# Sheet1.net
KiCad netlist of a schematic drawn in Altium Designer
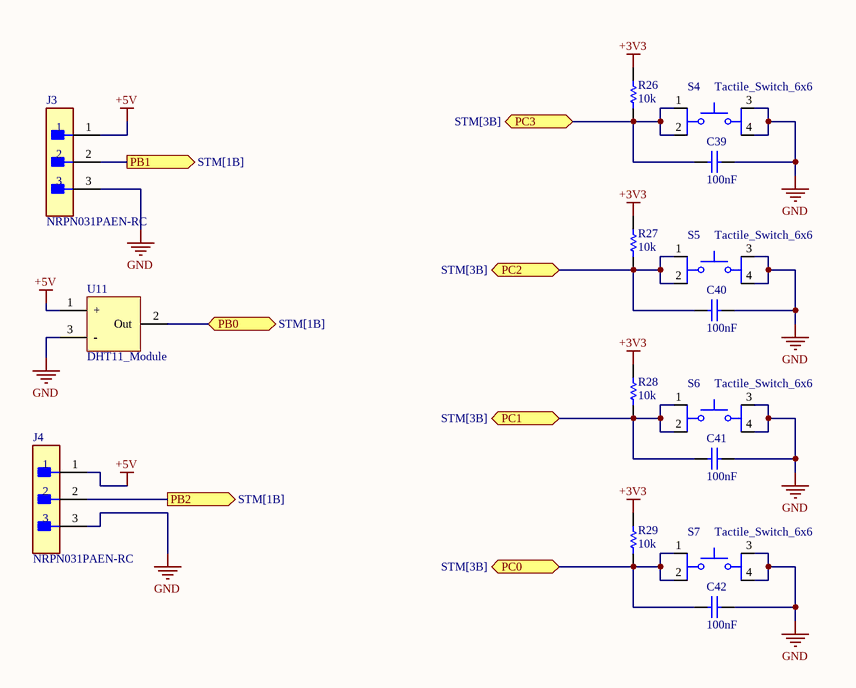
[diagram p0: Sheet1.SchDoc]

(export (version "E")
  (design (tool "Eeschema 10.0.6"))
  (components
    (comp (ref "C39")
      (value "100nF")
      (footprint "CAP_0603")
      (description "CAP, size 0603, 100nF")
      (libsource (lib "SMIOT_Lib_Schematic") (part "01060310410"))
    )
    (comp (ref "C40")
      (value "100nF")
      (footprint "CAP_0603")
      (description "CAP, size 0603, 100nF")
      (libsource (lib "SMIOT_Lib_Schematic") (part "01060310410"))
    )
    (comp (ref "C41")
      (value "100nF")
      (footprint "CAP_0603")
      (description "CAP, size 0603, 100nF")
      (libsource (lib "SMIOT_Lib_Schematic") (part "01060310410"))
    )
    (comp (ref "C42")
      (value "100nF")
      (footprint "CAP_0603")
      (description "CAP, size 0603, 100nF")
      (libsource (lib "SMIOT_Lib_Schematic") (part "01060310410"))
    )
    (comp (ref "J3")
      (value "NRPN031PAEN-RC")
      (footprint "FP-NRPN031PAEN-RC-MFG")
      (description "CONN HEADER VERT 3POS 2MM")
      (fields
        (field (name "OCTOPART") "https://octopart.com/nrpn031paen-rc-sullins-12817732")
        (field (name "MANUFACTURER") "Sullins")
      )
      (libsource (lib "Components - 31.10.24 - 03.11") (part "CMP-25680-000021-1"))
    )
    (comp (ref "J4")
      (value "NRPN031PAEN-RC")
      (footprint "FP-NRPN031PAEN-RC-MFG")
      (description "CONN HEADER VERT 3POS 2MM")
      (fields
        (field (name "OCTOPART") "https://octopart.com/nrpn031paen-rc-sullins-12817732")
        (field (name "MANUFACTURER") "Sullins")
      )
      (libsource (lib "Components - 31.10.24 - 03.11") (part "CMP-25680-000021-1"))
    )
    (comp (ref "R26")
      (value "10k")
      (footprint "resistor_0603")
      (description "RES, 10k Ohm, size 0603, 1%")
      (libsource (lib "SMIOT_Lib_Schematic") (part "0006031031"))
    )
    (comp (ref "R27")
      (value "10k")
      (footprint "resistor_0603")
      (description "RES, 10k Ohm, size 0603, 1%")
      (libsource (lib "SMIOT_Lib_Schematic") (part "0006031031"))
    )
    (comp (ref "R28")
      (value "10k")
      (footprint "resistor_0603")
      (description "RES, 10k Ohm, size 0603, 1%")
      (libsource (lib "SMIOT_Lib_Schematic") (part "0006031031"))
    )
    (comp (ref "R29")
      (value "10k")
      (footprint "resistor_0603")
      (description "RES, 10k Ohm, size 0603, 1%")
      (libsource (lib "SMIOT_Lib_Schematic") (part "0006031031"))
    )
    (comp (ref "S4")
      (value "Tactile_Switch_6x6")
      (footprint "Tactile_Switch_6x6")
      (description "Tactile Switch, 6x6mm")
      (libsource (lib "SMIOT_Lib_Schematic") (part "Tactile_Switch_6x6"))
    )
    (comp (ref "S5")
      (value "Tactile_Switch_6x6")
      (footprint "Tactile_Switch_6x6")
      (description "Tactile Switch, 6x6mm")
      (libsource (lib "SMIOT_Lib_Schematic") (part "Tactile_Switch_6x6"))
    )
    (comp (ref "S6")
      (value "Tactile_Switch_6x6")
      (footprint "Tactile_Switch_6x6")
      (description "Tactile Switch, 6x6mm")
      (libsource (lib "SMIOT_Lib_Schematic") (part "Tactile_Switch_6x6"))
    )
    (comp (ref "S7")
      (value "Tactile_Switch_6x6")
      (footprint "Tactile_Switch_6x6")
      (description "Tactile Switch, 6x6mm")
      (libsource (lib "SMIOT_Lib_Schematic") (part "Tactile_Switch_6x6"))
    )
    (comp (ref "U11")
      (value "DHT11_Module")
      (footprint "DHT11_Module")
      (description "Temperature & Humidity Sensor, 3.3V-5V, 5mA")
      (libsource (lib "SMIOT_Lib_Schematic") (part "DHT11_Module"))
    )
  )
  (nets
    (net (code "1") (name "+3V3") (class "Default")
      (node (ref "R26") (pin "1") (pinfunction "1_1") (pintype "passive"))
      (node (ref "R27") (pin "1") (pinfunction "1_1") (pintype "passive"))
      (node (ref "R28") (pin "1") (pinfunction "1_1") (pintype "passive"))
      (node (ref "R29") (pin "1") (pinfunction "1_1") (pintype "passive"))
    )
    (net (code "2") (name "+5V") (class "Default")
      (node (ref "J3") (pin "1") (pinfunction "1_1") (pintype "passive"))
      (node (ref "J4") (pin "1") (pinfunction "1_1") (pintype "passive"))
      (node (ref "U11") (pin "1") (pinfunction "+_1") (pintype "passive"))
    )
    (net (code "3") (name "/PB0") (class "Default")
      (node (ref "U11") (pin "2") (pinfunction "Out_2") (pintype "passive"))
    )
    (net (code "4") (name "/PB1") (class "Default")
      (node (ref "J3") (pin "2") (pinfunction "2_2") (pintype "passive"))
    )
    (net (code "5") (name "/PB2") (class "Default")
      (node (ref "J4") (pin "2") (pinfunction "2_2") (pintype "passive"))
    )
    (net (code "6") (name "/PC0") (class "Default")
      (node (ref "C42") (pin "1") (pinfunction "1_1") (pintype "passive"))
      (node (ref "R29") (pin "2") (pinfunction "2_2") (pintype "passive"))
      (node (ref "S7") (pin "1") (pinfunction "1_1") (pintype "passive"))
      (node (ref "S7") (pin "2") (pinfunction "2_2") (pintype "passive"))
    )
    (net (code "7") (name "/PC1") (class "Default")
      (node (ref "C41") (pin "1") (pinfunction "1_1") (pintype "passive"))
      (node (ref "R28") (pin "2") (pinfunction "2_2") (pintype "passive"))
      (node (ref "S6") (pin "1") (pinfunction "1_1") (pintype "passive"))
      (node (ref "S6") (pin "2") (pinfunction "2_2") (pintype "passive"))
    )
    (net (code "8") (name "/PC2") (class "Default")
      (node (ref "C40") (pin "1") (pinfunction "1_1") (pintype "passive"))
      (node (ref "R27") (pin "2") (pinfunction "2_2") (pintype "passive"))
      (node (ref "S5") (pin "1") (pinfunction "1_1") (pintype "passive"))
      (node (ref "S5") (pin "2") (pinfunction "2_2") (pintype "passive"))
    )
    (net (code "9") (name "/PC3") (class "Default")
      (node (ref "C39") (pin "1") (pinfunction "1_1") (pintype "passive"))
      (node (ref "R26") (pin "2") (pinfunction "2_2") (pintype "passive"))
      (node (ref "S4") (pin "1") (pinfunction "1_1") (pintype "passive"))
      (node (ref "S4") (pin "2") (pinfunction "2_2") (pintype "passive"))
    )
    (net (code "10") (name "GND") (class "Default")
      (node (ref "C39") (pin "2") (pinfunction "2_2") (pintype "passive"))
      (node (ref "C40") (pin "2") (pinfunction "2_2") (pintype "passive"))
      (node (ref "C41") (pin "2") (pinfunction "2_2") (pintype "passive"))
      (node (ref "C42") (pin "2") (pinfunction "2_2") (pintype "passive"))
      (node (ref "J3") (pin "3") (pinfunction "3_3") (pintype "passive"))
      (node (ref "J4") (pin "3") (pinfunction "3_3") (pintype "passive"))
      (node (ref "S4") (pin "3") (pinfunction "3_3") (pintype "passive"))
      (node (ref "S4") (pin "4") (pinfunction "4_4") (pintype "passive"))
      (node (ref "S5") (pin "3") (pinfunction "3_3") (pintype "passive"))
      (node (ref "S5") (pin "4") (pinfunction "4_4") (pintype "passive"))
      (node (ref "S6") (pin "3") (pinfunction "3_3") (pintype "passive"))
      (node (ref "S6") (pin "4") (pinfunction "4_4") (pintype "passive"))
      (node (ref "S7") (pin "3") (pinfunction "3_3") (pintype "passive"))
      (node (ref "S7") (pin "4") (pinfunction "4_4") (pintype "passive"))
      (node (ref "U11") (pin "3") (pinfunction "-_3") (pintype "power_in"))
    )
  )
)
